# 07_-_QSFP28_1.net
KiCad netlist of a schematic drawn in Altium Designer
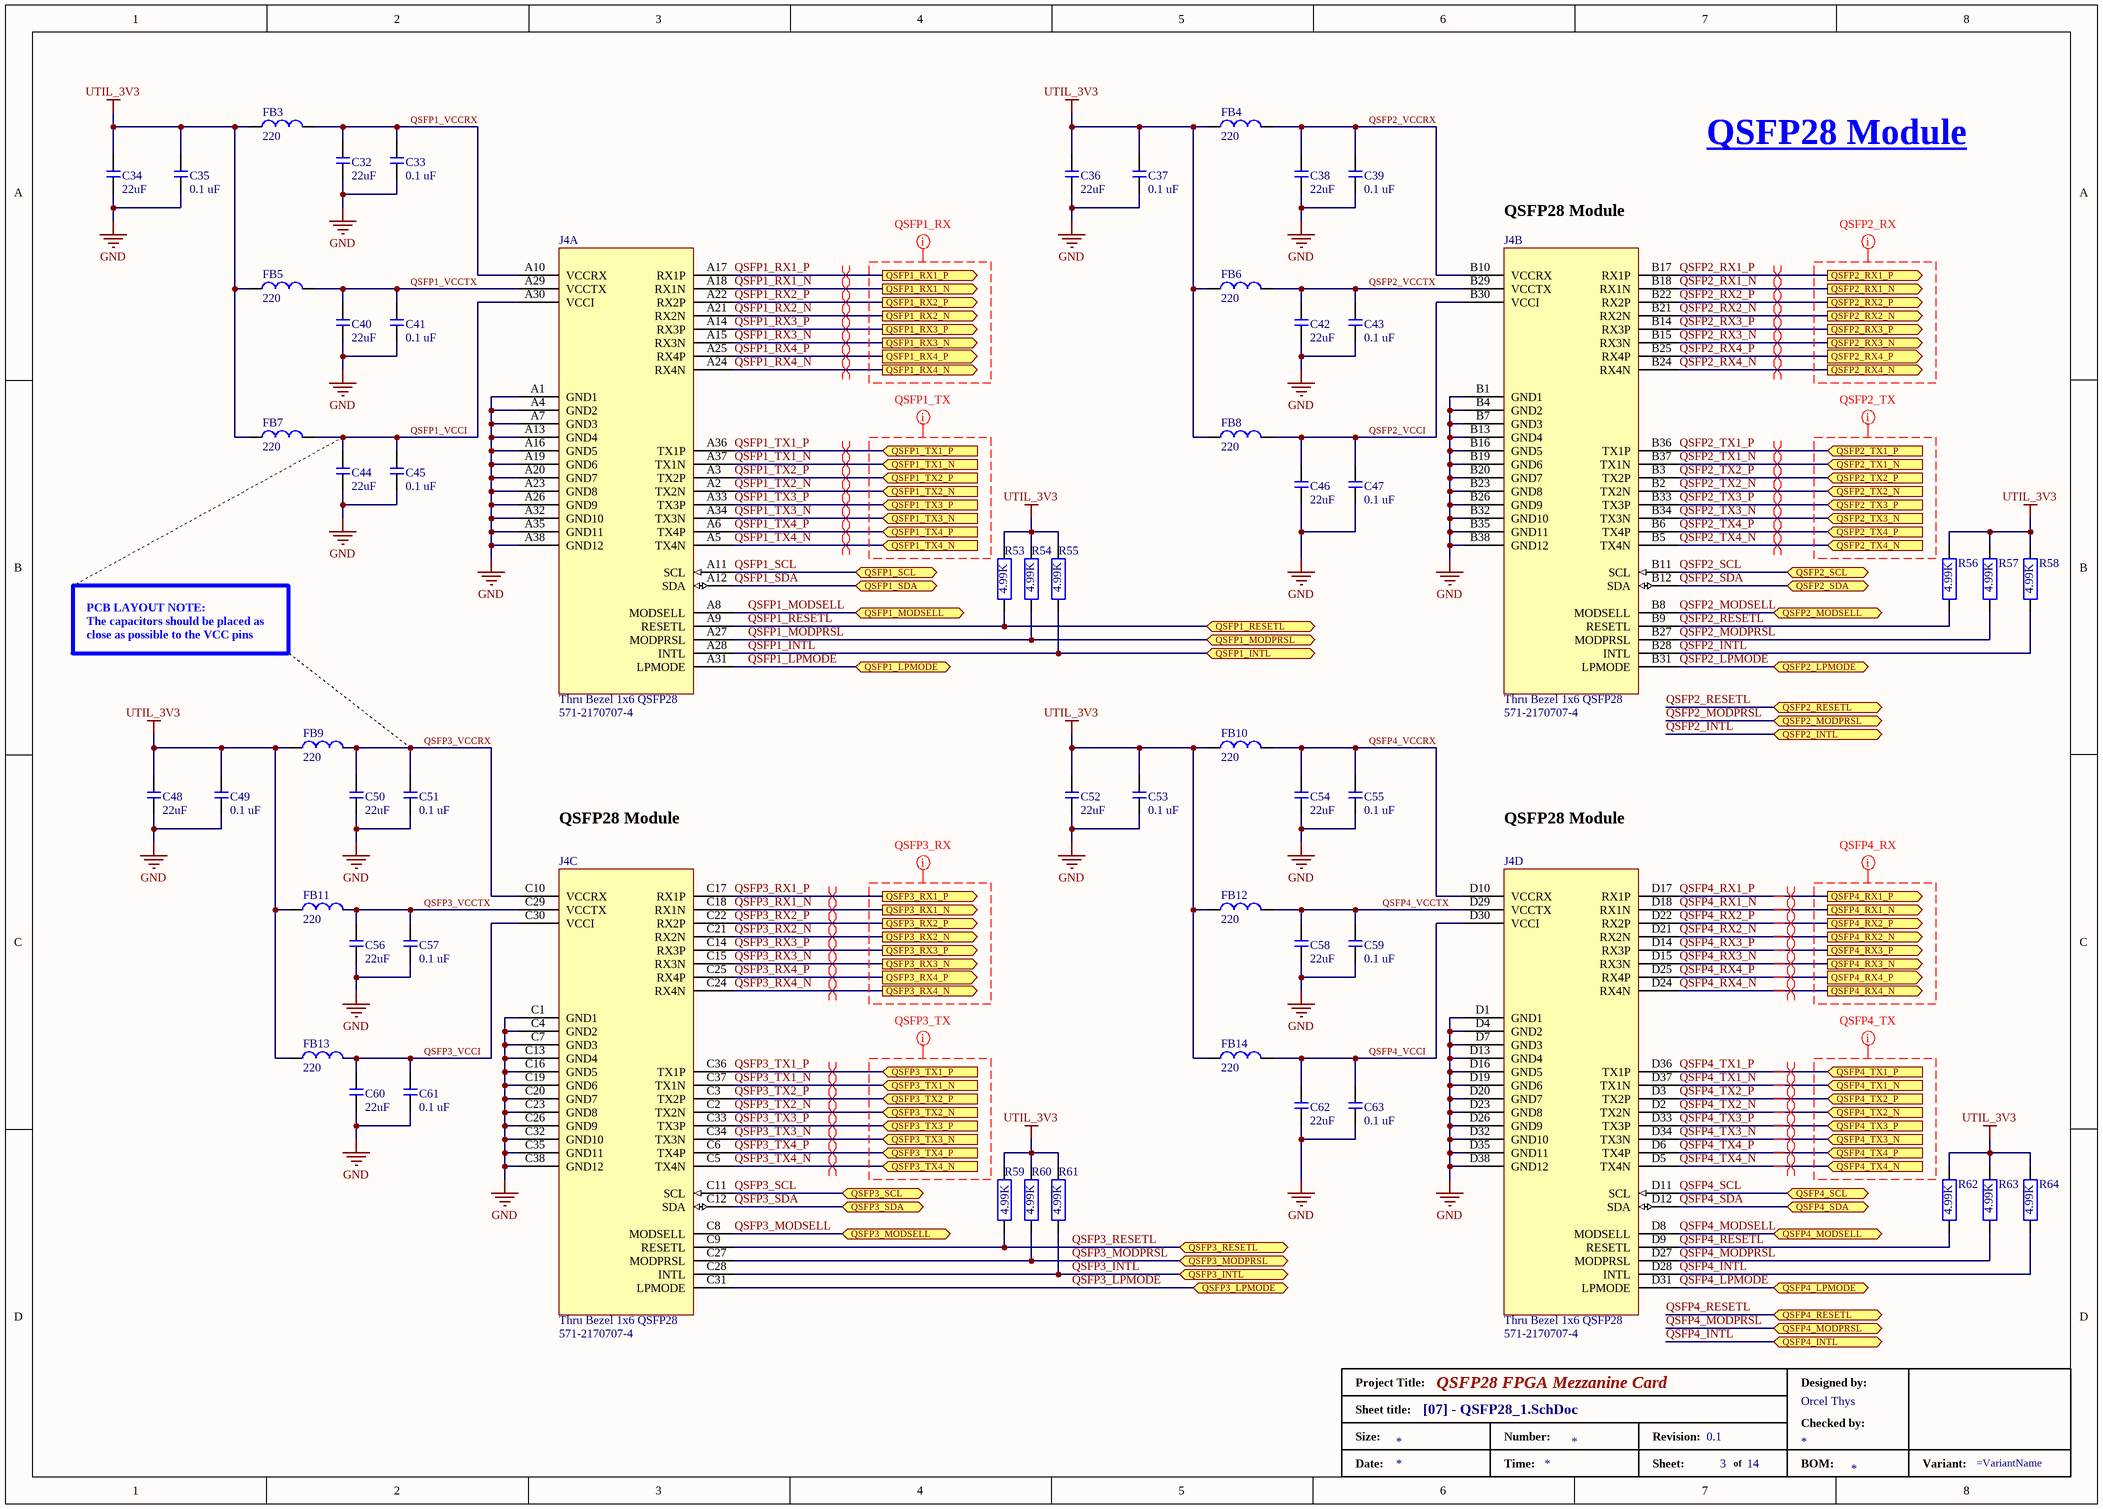
[diagram p0: [07] - QSFP28_1.SchDoc]

(export (version "E")
  (design (tool "Eeschema 10.0.6"))
  (components
    (comp (ref "C32")
      (value "22uF")
      (footprint "C2012")
      (description "Cap Series 0805 22 uF 35 V ±20 % Tolerance X5R SMT Multilayer Ceramic Capacitor")
      (fields
        (field (name "MANUFACTURER") "TDK")
        (field (name "MANUFACTURER PART NUMBER") "C2012X5R1V226M125AC")
      )
      (libsource (lib "QSFP28_FMC_lib") (part "C2012X5R1V226M125AC"))
    )
    (comp (ref "C33")
      (value "0.1 uF")
      (footprint "C0402")
      (description "Cap 0402 0.1 uF 50 V ±10 % Tolerance X7R Surface Mount Multilayer Ceramic Capacitor")
      (fields
        (field (name "MANUFACTURER") "Taiyo Yuden")
        (field (name "MANUFACTURER PART NUMBER") "UMK105B7104KV-FR")
      )
      (libsource (lib "QSFP28_FMC_lib") (part "UMK105B7104KV-FR"))
    )
    (comp (ref "C34")
      (value "22uF")
      (footprint "C2012")
      (description "Cap Series 0805 22 uF 35 V ±20 % Tolerance X5R SMT Multilayer Ceramic Capacitor")
      (fields
        (field (name "MANUFACTURER") "TDK")
        (field (name "MANUFACTURER PART NUMBER") "C2012X5R1V226M125AC")
      )
      (libsource (lib "QSFP28_FMC_lib") (part "C2012X5R1V226M125AC"))
    )
    (comp (ref "C35")
      (value "0.1 uF")
      (footprint "C0402")
      (description "Cap 0402 0.1 uF 50 V ±10 % Tolerance X7R Surface Mount Multilayer Ceramic Capacitor")
      (fields
        (field (name "MANUFACTURER") "Taiyo Yuden")
        (field (name "MANUFACTURER PART NUMBER") "UMK105B7104KV-FR")
      )
      (libsource (lib "QSFP28_FMC_lib") (part "UMK105B7104KV-FR"))
    )
    (comp (ref "C36")
      (value "22uF")
      (footprint "C2012")
      (description "Cap Series 0805 22 uF 35 V ±20 % Tolerance X5R SMT Multilayer Ceramic Capacitor")
      (fields
        (field (name "MANUFACTURER") "TDK")
        (field (name "MANUFACTURER PART NUMBER") "C2012X5R1V226M125AC")
      )
      (libsource (lib "QSFP28_FMC_lib") (part "C2012X5R1V226M125AC"))
    )
    (comp (ref "C37")
      (value "0.1 uF")
      (footprint "C0402")
      (description "Cap 0402 0.1 uF 50 V ±10 % Tolerance X7R Surface Mount Multilayer Ceramic Capacitor")
      (fields
        (field (name "MANUFACTURER") "Taiyo Yuden")
        (field (name "MANUFACTURER PART NUMBER") "UMK105B7104KV-FR")
      )
      (libsource (lib "QSFP28_FMC_lib") (part "UMK105B7104KV-FR"))
    )
    (comp (ref "C38")
      (value "22uF")
      (footprint "C2012")
      (description "Cap Series 0805 22 uF 35 V ±20 % Tolerance X5R SMT Multilayer Ceramic Capacitor")
      (fields
        (field (name "MANUFACTURER") "TDK")
        (field (name "MANUFACTURER PART NUMBER") "C2012X5R1V226M125AC")
      )
      (libsource (lib "QSFP28_FMC_lib") (part "C2012X5R1V226M125AC"))
    )
    (comp (ref "C39")
      (value "0.1 uF")
      (footprint "C0402")
      (description "Cap 0402 0.1 uF 50 V ±10 % Tolerance X7R Surface Mount Multilayer Ceramic Capacitor")
      (fields
        (field (name "MANUFACTURER") "Taiyo Yuden")
        (field (name "MANUFACTURER PART NUMBER") "UMK105B7104KV-FR")
      )
      (libsource (lib "QSFP28_FMC_lib") (part "UMK105B7104KV-FR"))
    )
    (comp (ref "C40")
      (value "22uF")
      (footprint "C2012")
      (description "Cap Series 0805 22 uF 35 V ±20 % Tolerance X5R SMT Multilayer Ceramic Capacitor")
      (fields
        (field (name "MANUFACTURER") "TDK")
        (field (name "MANUFACTURER PART NUMBER") "C2012X5R1V226M125AC")
      )
      (libsource (lib "QSFP28_FMC_lib") (part "C2012X5R1V226M125AC"))
    )
    (comp (ref "C41")
      (value "0.1 uF")
      (footprint "C0402")
      (description "Cap 0402 0.1 uF 50 V ±10 % Tolerance X7R Surface Mount Multilayer Ceramic Capacitor")
      (fields
        (field (name "MANUFACTURER") "Taiyo Yuden")
        (field (name "MANUFACTURER PART NUMBER") "UMK105B7104KV-FR")
      )
      (libsource (lib "QSFP28_FMC_lib") (part "UMK105B7104KV-FR"))
    )
    (comp (ref "C42")
      (value "22uF")
      (footprint "C2012")
      (description "Cap Series 0805 22 uF 35 V ±20 % Tolerance X5R SMT Multilayer Ceramic Capacitor")
      (fields
        (field (name "MANUFACTURER") "TDK")
        (field (name "MANUFACTURER PART NUMBER") "C2012X5R1V226M125AC")
      )
      (libsource (lib "QSFP28_FMC_lib") (part "C2012X5R1V226M125AC"))
    )
    (comp (ref "C43")
      (value "0.1 uF")
      (footprint "C0402")
      (description "Cap 0402 0.1 uF 50 V ±10 % Tolerance X7R Surface Mount Multilayer Ceramic Capacitor")
      (fields
        (field (name "MANUFACTURER") "Taiyo Yuden")
        (field (name "MANUFACTURER PART NUMBER") "UMK105B7104KV-FR")
      )
      (libsource (lib "QSFP28_FMC_lib") (part "UMK105B7104KV-FR"))
    )
    (comp (ref "C44")
      (value "22uF")
      (footprint "C2012")
      (description "Cap Series 0805 22 uF 35 V ±20 % Tolerance X5R SMT Multilayer Ceramic Capacitor")
      (fields
        (field (name "MANUFACTURER") "TDK")
        (field (name "MANUFACTURER PART NUMBER") "C2012X5R1V226M125AC")
      )
      (libsource (lib "QSFP28_FMC_lib") (part "C2012X5R1V226M125AC"))
    )
    (comp (ref "C45")
      (value "0.1 uF")
      (footprint "C0402")
      (description "Cap 0402 0.1 uF 50 V ±10 % Tolerance X7R Surface Mount Multilayer Ceramic Capacitor")
      (fields
        (field (name "MANUFACTURER") "Taiyo Yuden")
        (field (name "MANUFACTURER PART NUMBER") "UMK105B7104KV-FR")
      )
      (libsource (lib "QSFP28_FMC_lib") (part "UMK105B7104KV-FR"))
    )
    (comp (ref "C46")
      (value "22uF")
      (footprint "C2012")
      (description "Cap Series 0805 22 uF 35 V ±20 % Tolerance X5R SMT Multilayer Ceramic Capacitor")
      (fields
        (field (name "MANUFACTURER") "TDK")
        (field (name "MANUFACTURER PART NUMBER") "C2012X5R1V226M125AC")
      )
      (libsource (lib "QSFP28_FMC_lib") (part "C2012X5R1V226M125AC"))
    )
    (comp (ref "C47")
      (value "0.1 uF")
      (footprint "C0402")
      (description "Cap 0402 0.1 uF 50 V ±10 % Tolerance X7R Surface Mount Multilayer Ceramic Capacitor")
      (fields
        (field (name "MANUFACTURER") "Taiyo Yuden")
        (field (name "MANUFACTURER PART NUMBER") "UMK105B7104KV-FR")
      )
      (libsource (lib "QSFP28_FMC_lib") (part "UMK105B7104KV-FR"))
    )
    (comp (ref "C48")
      (value "22uF")
      (footprint "C2012")
      (description "Cap Series 0805 22 uF 35 V ±20 % Tolerance X5R SMT Multilayer Ceramic Capacitor")
      (fields
        (field (name "MANUFACTURER") "TDK")
        (field (name "MANUFACTURER PART NUMBER") "C2012X5R1V226M125AC")
      )
      (libsource (lib "QSFP28_FMC_lib") (part "C2012X5R1V226M125AC"))
    )
    (comp (ref "C49")
      (value "0.1 uF")
      (footprint "C0402")
      (description "Cap 0402 0.1 uF 50 V ±10 % Tolerance X7R Surface Mount Multilayer Ceramic Capacitor")
      (fields
        (field (name "MANUFACTURER") "Taiyo Yuden")
        (field (name "MANUFACTURER PART NUMBER") "UMK105B7104KV-FR")
      )
      (libsource (lib "QSFP28_FMC_lib") (part "UMK105B7104KV-FR"))
    )
    (comp (ref "C50")
      (value "22uF")
      (footprint "C2012")
      (description "Cap Series 0805 22 uF 35 V ±20 % Tolerance X5R SMT Multilayer Ceramic Capacitor")
      (fields
        (field (name "MANUFACTURER") "TDK")
        (field (name "MANUFACTURER PART NUMBER") "C2012X5R1V226M125AC")
      )
      (libsource (lib "QSFP28_FMC_lib") (part "C2012X5R1V226M125AC"))
    )
    (comp (ref "C51")
      (value "0.1 uF")
      (footprint "C0402")
      (description "Cap 0402 0.1 uF 50 V ±10 % Tolerance X7R Surface Mount Multilayer Ceramic Capacitor")
      (fields
        (field (name "MANUFACTURER") "Taiyo Yuden")
        (field (name "MANUFACTURER PART NUMBER") "UMK105B7104KV-FR")
      )
      (libsource (lib "QSFP28_FMC_lib") (part "UMK105B7104KV-FR"))
    )
    (comp (ref "C52")
      (value "22uF")
      (footprint "C2012")
      (description "Cap Series 0805 22 uF 35 V ±20 % Tolerance X5R SMT Multilayer Ceramic Capacitor")
      (fields
        (field (name "MANUFACTURER") "TDK")
        (field (name "MANUFACTURER PART NUMBER") "C2012X5R1V226M125AC")
      )
      (libsource (lib "QSFP28_FMC_lib") (part "C2012X5R1V226M125AC"))
    )
    (comp (ref "C53")
      (value "0.1 uF")
      (footprint "C0402")
      (description "Cap 0402 0.1 uF 50 V ±10 % Tolerance X7R Surface Mount Multilayer Ceramic Capacitor")
      (fields
        (field (name "MANUFACTURER") "Taiyo Yuden")
        (field (name "MANUFACTURER PART NUMBER") "UMK105B7104KV-FR")
      )
      (libsource (lib "QSFP28_FMC_lib") (part "UMK105B7104KV-FR"))
    )
    (comp (ref "C54")
      (value "22uF")
      (footprint "C2012")
      (description "Cap Series 0805 22 uF 35 V ±20 % Tolerance X5R SMT Multilayer Ceramic Capacitor")
      (fields
        (field (name "MANUFACTURER") "TDK")
        (field (name "MANUFACTURER PART NUMBER") "C2012X5R1V226M125AC")
      )
      (libsource (lib "QSFP28_FMC_lib") (part "C2012X5R1V226M125AC"))
    )
    (comp (ref "C55")
      (value "0.1 uF")
      (footprint "C0402")
      (description "Cap 0402 0.1 uF 50 V ±10 % Tolerance X7R Surface Mount Multilayer Ceramic Capacitor")
      (fields
        (field (name "MANUFACTURER") "Taiyo Yuden")
        (field (name "MANUFACTURER PART NUMBER") "UMK105B7104KV-FR")
      )
      (libsource (lib "QSFP28_FMC_lib") (part "UMK105B7104KV-FR"))
    )
    (comp (ref "C56")
      (value "22uF")
      (footprint "C2012")
      (description "Cap Series 0805 22 uF 35 V ±20 % Tolerance X5R SMT Multilayer Ceramic Capacitor")
      (fields
        (field (name "MANUFACTURER") "TDK")
        (field (name "MANUFACTURER PART NUMBER") "C2012X5R1V226M125AC")
      )
      (libsource (lib "QSFP28_FMC_lib") (part "C2012X5R1V226M125AC"))
    )
    (comp (ref "C57")
      (value "0.1 uF")
      (footprint "C0402")
      (description "Cap 0402 0.1 uF 50 V ±10 % Tolerance X7R Surface Mount Multilayer Ceramic Capacitor")
      (fields
        (field (name "MANUFACTURER") "Taiyo Yuden")
        (field (name "MANUFACTURER PART NUMBER") "UMK105B7104KV-FR")
      )
      (libsource (lib "QSFP28_FMC_lib") (part "UMK105B7104KV-FR"))
    )
    (comp (ref "C58")
      (value "22uF")
      (footprint "C2012")
      (description "Cap Series 0805 22 uF 35 V ±20 % Tolerance X5R SMT Multilayer Ceramic Capacitor")
      (fields
        (field (name "MANUFACTURER") "TDK")
        (field (name "MANUFACTURER PART NUMBER") "C2012X5R1V226M125AC")
      )
      (libsource (lib "QSFP28_FMC_lib") (part "C2012X5R1V226M125AC"))
    )
    (comp (ref "C59")
      (value "0.1 uF")
      (footprint "C0402")
      (description "Cap 0402 0.1 uF 50 V ±10 % Tolerance X7R Surface Mount Multilayer Ceramic Capacitor")
      (fields
        (field (name "MANUFACTURER") "Taiyo Yuden")
        (field (name "MANUFACTURER PART NUMBER") "UMK105B7104KV-FR")
      )
      (libsource (lib "QSFP28_FMC_lib") (part "UMK105B7104KV-FR"))
    )
    (comp (ref "C60")
      (value "22uF")
      (footprint "C2012")
      (description "Cap Series 0805 22 uF 35 V ±20 % Tolerance X5R SMT Multilayer Ceramic Capacitor")
      (fields
        (field (name "MANUFACTURER") "TDK")
        (field (name "MANUFACTURER PART NUMBER") "C2012X5R1V226M125AC")
      )
      (libsource (lib "QSFP28_FMC_lib") (part "C2012X5R1V226M125AC"))
    )
    (comp (ref "C61")
      (value "0.1 uF")
      (footprint "C0402")
      (description "Cap 0402 0.1 uF 50 V ±10 % Tolerance X7R Surface Mount Multilayer Ceramic Capacitor")
      (fields
        (field (name "MANUFACTURER") "Taiyo Yuden")
        (field (name "MANUFACTURER PART NUMBER") "UMK105B7104KV-FR")
      )
      (libsource (lib "QSFP28_FMC_lib") (part "UMK105B7104KV-FR"))
    )
    (comp (ref "C62")
      (value "22uF")
      (footprint "C2012")
      (description "Cap Series 0805 22 uF 35 V ±20 % Tolerance X5R SMT Multilayer Ceramic Capacitor")
      (fields
        (field (name "MANUFACTURER") "TDK")
        (field (name "MANUFACTURER PART NUMBER") "C2012X5R1V226M125AC")
      )
      (libsource (lib "QSFP28_FMC_lib") (part "C2012X5R1V226M125AC"))
    )
    (comp (ref "C63")
      (value "0.1 uF")
      (footprint "C0402")
      (description "Cap 0402 0.1 uF 50 V ±10 % Tolerance X7R Surface Mount Multilayer Ceramic Capacitor")
      (fields
        (field (name "MANUFACTURER") "Taiyo Yuden")
        (field (name "MANUFACTURER PART NUMBER") "UMK105B7104KV-FR")
      )
      (libsource (lib "QSFP28_FMC_lib") (part "UMK105B7104KV-FR"))
    )
    (comp (ref "FB3")
      (value "220")
      (footprint "BEADC1608X75N")
      (description "0603 220Ω ±25% DCR=0.050Ω 2.2A")
      (fields
        (field (name "MANUFACTURER") "TDK")
        (field (name "MANUFACTURER PART NUMBER") "MPZ1608S221ATA00")
      )
      (libsource (lib "QSFP28_FMC_lib") (part "MPZ1608S221ATA00"))
    )
    (comp (ref "FB4")
      (value "220")
      (footprint "BEADC1608X75N")
      (description "0603 220Ω ±25% DCR=0.050Ω 2.2A")
      (fields
        (field (name "MANUFACTURER") "TDK")
        (field (name "MANUFACTURER PART NUMBER") "MPZ1608S221ATA00")
      )
      (libsource (lib "QSFP28_FMC_lib") (part "MPZ1608S221ATA00"))
    )
    (comp (ref "FB5")
      (value "220")
      (footprint "BEADC1608X75N")
      (description "0603 220Ω ±25% DCR=0.050Ω 2.2A")
      (fields
        (field (name "MANUFACTURER") "TDK")
        (field (name "MANUFACTURER PART NUMBER") "MPZ1608S221ATA00")
      )
      (libsource (lib "QSFP28_FMC_lib") (part "MPZ1608S221ATA00"))
    )
    (comp (ref "FB6")
      (value "220")
      (footprint "BEADC1608X75N")
      (description "0603 220Ω ±25% DCR=0.050Ω 2.2A")
      (fields
        (field (name "MANUFACTURER") "TDK")
        (field (name "MANUFACTURER PART NUMBER") "MPZ1608S221ATA00")
      )
      (libsource (lib "QSFP28_FMC_lib") (part "MPZ1608S221ATA00"))
    )
    (comp (ref "FB7")
      (value "220")
      (footprint "BEADC1608X75N")
      (description "0603 220Ω ±25% DCR=0.050Ω 2.2A")
      (fields
        (field (name "MANUFACTURER") "TDK")
        (field (name "MANUFACTURER PART NUMBER") "MPZ1608S221ATA00")
      )
      (libsource (lib "QSFP28_FMC_lib") (part "MPZ1608S221ATA00"))
    )
    (comp (ref "FB8")
      (value "220")
      (footprint "BEADC1608X75N")
      (description "0603 220Ω ±25% DCR=0.050Ω 2.2A")
      (fields
        (field (name "MANUFACTURER") "TDK")
        (field (name "MANUFACTURER PART NUMBER") "MPZ1608S221ATA00")
      )
      (libsource (lib "QSFP28_FMC_lib") (part "MPZ1608S221ATA00"))
    )
    (comp (ref "FB9")
      (value "220")
      (footprint "BEADC1608X75N")
      (description "0603 220Ω ±25% DCR=0.050Ω 2.2A")
      (fields
        (field (name "MANUFACTURER") "TDK")
        (field (name "MANUFACTURER PART NUMBER") "MPZ1608S221ATA00")
      )
      (libsource (lib "QSFP28_FMC_lib") (part "MPZ1608S221ATA00"))
    )
    (comp (ref "FB10")
      (value "220")
      (footprint "BEADC1608X75N")
      (description "0603 220Ω ±25% DCR=0.050Ω 2.2A")
      (fields
        (field (name "MANUFACTURER") "TDK")
        (field (name "MANUFACTURER PART NUMBER") "MPZ1608S221ATA00")
      )
      (libsource (lib "QSFP28_FMC_lib") (part "MPZ1608S221ATA00"))
    )
    (comp (ref "FB11")
      (value "220")
      (footprint "BEADC1608X75N")
      (description "0603 220Ω ±25% DCR=0.050Ω 2.2A")
      (fields
        (field (name "MANUFACTURER") "TDK")
        (field (name "MANUFACTURER PART NUMBER") "MPZ1608S221ATA00")
      )
      (libsource (lib "QSFP28_FMC_lib") (part "MPZ1608S221ATA00"))
    )
    (comp (ref "FB12")
      (value "220")
      (footprint "BEADC1608X75N")
      (description "0603 220Ω ±25% DCR=0.050Ω 2.2A")
      (fields
        (field (name "MANUFACTURER") "TDK")
        (field (name "MANUFACTURER PART NUMBER") "MPZ1608S221ATA00")
      )
      (libsource (lib "QSFP28_FMC_lib") (part "MPZ1608S221ATA00"))
    )
    (comp (ref "FB13")
      (value "220")
      (footprint "BEADC1608X75N")
      (description "0603 220Ω ±25% DCR=0.050Ω 2.2A")
      (fields
        (field (name "MANUFACTURER") "TDK")
        (field (name "MANUFACTURER PART NUMBER") "MPZ1608S221ATA00")
      )
      (libsource (lib "QSFP28_FMC_lib") (part "MPZ1608S221ATA00"))
    )
    (comp (ref "FB14")
      (value "220")
      (footprint "BEADC1608X75N")
      (description "0603 220Ω ±25% DCR=0.050Ω 2.2A")
      (fields
        (field (name "MANUFACTURER") "TDK")
        (field (name "MANUFACTURER PART NUMBER") "MPZ1608S221ATA00")
      )
      (libsource (lib "QSFP28_FMC_lib") (part "MPZ1608S221ATA00"))
    )
    (comp (ref "J4")
      (value "Thru Bezel 1x6 QSFP28")
      (footprint "TE_2170707-4")
      (description "Cage Assy, 1X6, QSFP28, Spring, Hs")
      (fields
        (field (name "MANUFACTURER") "TE Connectivity AMP")
        (field (name "MANUFACTURER PART NUMBER") "2170707-4")
        (field (name "SUPPLIER PART NUMBER 1") "571-2170707-4")
      )
      (libsource (lib "QSFP28_FMC_lib") (part "2170707-4"))
    )
    (comp (ref "R53")
      (value "4.99K")
      (footprint "R0402")
      (description "RES SMD 4.99K OHM 1% 1/10W 0402")
      (fields
        (field (name "MANUFACTURER") "Panasonic")
        (field (name "MANUFACTURER PART NUMBER") "ERJ-2RKF4991X")
      )
      (libsource (lib "QSFP28_FMC_lib") (part "ERJ-2RKF4991X"))
    )
    (comp (ref "R54")
      (value "4.99K")
      (footprint "R0402")
      (description "RES SMD 4.99K OHM 1% 1/10W 0402")
      (fields
        (field (name "MANUFACTURER") "Panasonic")
        (field (name "MANUFACTURER PART NUMBER") "ERJ-2RKF4991X")
      )
      (libsource (lib "QSFP28_FMC_lib") (part "ERJ-2RKF4991X"))
    )
    (comp (ref "R55")
      (value "4.99K")
      (footprint "R0402")
      (description "RES SMD 4.99K OHM 1% 1/10W 0402")
      (fields
        (field (name "MANUFACTURER") "Panasonic")
        (field (name "MANUFACTURER PART NUMBER") "ERJ-2RKF4991X")
      )
      (libsource (lib "QSFP28_FMC_lib") (part "ERJ-2RKF4991X"))
    )
    (comp (ref "R56")
      (value "4.99K")
      (footprint "R0402")
      (description "RES SMD 4.99K OHM 1% 1/10W 0402")
      (fields
        (field (name "MANUFACTURER") "Panasonic")
        (field (name "MANUFACTURER PART NUMBER") "ERJ-2RKF4991X")
      )
      (libsource (lib "QSFP28_FMC_lib") (part "ERJ-2RKF4991X"))
    )
    (comp (ref "R57")
      (value "4.99K")
      (footprint "R0402")
      (description "RES SMD 4.99K OHM 1% 1/10W 0402")
      (fields
        (field (name "MANUFACTURER") "Panasonic")
        (field (name "MANUFACTURER PART NUMBER") "ERJ-2RKF4991X")
      )
      (libsource (lib "QSFP28_FMC_lib") (part "ERJ-2RKF4991X"))
    )
    (comp (ref "R58")
      (value "4.99K")
      (footprint "R0402")
      (description "RES SMD 4.99K OHM 1% 1/10W 0402")
      (fields
        (field (name "MANUFACTURER") "Panasonic")
        (field (name "MANUFACTURER PART NUMBER") "ERJ-2RKF4991X")
      )
      (libsource (lib "QSFP28_FMC_lib") (part "ERJ-2RKF4991X"))
    )
    (comp (ref "R59")
      (value "4.99K")
      (footprint "R0402")
      (description "RES SMD 4.99K OHM 1% 1/10W 0402")
      (fields
        (field (name "MANUFACTURER") "Panasonic")
        (field (name "MANUFACTURER PART NUMBER") "ERJ-2RKF4991X")
      )
      (libsource (lib "QSFP28_FMC_lib") (part "ERJ-2RKF4991X"))
    )
    (comp (ref "R60")
      (value "4.99K")
      (footprint "R0402")
      (description "RES SMD 4.99K OHM 1% 1/10W 0402")
      (fields
        (field (name "MANUFACTURER") "Panasonic")
        (field (name "MANUFACTURER PART NUMBER") "ERJ-2RKF4991X")
      )
      (libsource (lib "QSFP28_FMC_lib") (part "ERJ-2RKF4991X"))
    )
    (comp (ref "R61")
      (value "4.99K")
      (footprint "R0402")
      (description "RES SMD 4.99K OHM 1% 1/10W 0402")
      (fields
        (field (name "MANUFACTURER") "Panasonic")
        (field (name "MANUFACTURER PART NUMBER") "ERJ-2RKF4991X")
      )
      (libsource (lib "QSFP28_FMC_lib") (part "ERJ-2RKF4991X"))
    )
    (comp (ref "R62")
      (value "4.99K")
      (footprint "R0402")
      (description "RES SMD 4.99K OHM 1% 1/10W 0402")
      (fields
        (field (name "MANUFACTURER") "Panasonic")
        (field (name "MANUFACTURER PART NUMBER") "ERJ-2RKF4991X")
      )
      (libsource (lib "QSFP28_FMC_lib") (part "ERJ-2RKF4991X"))
    )
    (comp (ref "R63")
      (value "4.99K")
      (footprint "R0402")
      (description "RES SMD 4.99K OHM 1% 1/10W 0402")
      (fields
        (field (name "MANUFACTURER") "Panasonic")
        (field (name "MANUFACTURER PART NUMBER") "ERJ-2RKF4991X")
      )
      (libsource (lib "QSFP28_FMC_lib") (part "ERJ-2RKF4991X"))
    )
    (comp (ref "R64")
      (value "4.99K")
      (footprint "R0402")
      (description "RES SMD 4.99K OHM 1% 1/10W 0402")
      (fields
        (field (name "MANUFACTURER") "Panasonic")
        (field (name "MANUFACTURER PART NUMBER") "ERJ-2RKF4991X")
      )
      (libsource (lib "QSFP28_FMC_lib") (part "ERJ-2RKF4991X"))
    )
  )
  (nets
    (net (code "1") (name "/QSFP1_INTL") (class "Default")
      (node (ref "J4") (pin "A28") (pinfunction "INTL_A28") (pintype "passive"))
      (node (ref "R55") (pin "1") (pintype "passive"))
    )
    (net (code "2") (name "/QSFP1_LPMODE") (class "Default")
      (node (ref "J4") (pin "A31") (pinfunction "LPMODE_A31") (pintype "passive"))
    )
    (net (code "3") (name "/QSFP1_MODPRSL") (class "Default")
      (node (ref "J4") (pin "A27") (pinfunction "MODPRSL_A27") (pintype "passive"))
      (node (ref "R54") (pin "1") (pintype "passive"))
    )
    (net (code "4") (name "/QSFP1_MODSELL") (class "Default")
      (node (ref "J4") (pin "A8") (pinfunction "MODSELL_A8") (pintype "passive"))
    )
    (net (code "5") (name "/QSFP1_RESETL") (class "Default")
      (node (ref "J4") (pin "A9") (pinfunction "RESETL_A9") (pintype "passive"))
      (node (ref "R53") (pin "1") (pintype "passive"))
    )
    (net (code "6") (name "/QSFP1_RX1_N") (class "Default")
      (node (ref "J4") (pin "A18") (pinfunction "RX1N_A18") (pintype "passive"))
    )
    (net (code "7") (name "/QSFP1_RX1_P") (class "Default")
      (node (ref "J4") (pin "A17") (pinfunction "RX1P_A17") (pintype "passive"))
    )
    (net (code "8") (name "/QSFP1_RX2_N") (class "Default")
      (node (ref "J4") (pin "A21") (pinfunction "RX2N_A21") (pintype "passive"))
    )
    (net (code "9") (name "/QSFP1_RX2_P") (class "Default")
      (node (ref "J4") (pin "A22") (pinfunction "RX2P_A22") (pintype "passive"))
    )
    (net (code "10") (name "/QSFP1_RX3_N") (class "Default")
      (node (ref "J4") (pin "A15") (pinfunction "RX3N_A15") (pintype "passive"))
    )
    (net (code "11") (name "/QSFP1_RX3_P") (class "Default")
      (node (ref "J4") (pin "A14") (pinfunction "RX3P_A14") (pintype "passive"))
    )
    (net (code "12") (name "/QSFP1_RX4_N") (class "Default")
      (node (ref "J4") (pin "A24") (pinfunction "RX4N_A24") (pintype "passive"))
    )
    (net (code "13") (name "/QSFP1_RX4_P") (class "Default")
      (node (ref "J4") (pin "A25") (pinfunction "RX4P_A25") (pintype "passive"))
    )
    (net (code "14") (name "/QSFP1_SCL") (class "Default")
      (node (ref "J4") (pin "A11") (pinfunction "SCL_A11") (pintype "input"))
    )
    (net (code "15") (name "/QSFP1_SDA") (class "Default")
      (node (ref "J4") (pin "A12") (pinfunction "SDA_A12") (pintype "bidirectional"))
    )
    (net (code "16") (name "/QSFP1_TX1_N") (class "Default")
      (node (ref "J4") (pin "A37") (pinfunction "TX1N_A37") (pintype "passive"))
    )
    (net (code "17") (name "/QSFP1_TX1_P") (class "Default")
      (node (ref "J4") (pin "A36") (pinfunction "TX1P_A36") (pintype "passive"))
    )
    (net (code "18") (name "/QSFP1_TX2_N") (class "Default")
      (node (ref "J4") (pin "A2") (pinfunction "TX2N_A2") (pintype "passive"))
    )
    (net (code "19") (name "/QSFP1_TX2_P") (class "Default")
      (node (ref "J4") (pin "A3") (pinfunction "TX2P_A3") (pintype "passive"))
    )
    (net (code "20") (name "/QSFP1_TX3_N") (class "Default")
      (node (ref "J4") (pin "A34") (pinfunction "TX3N_A34") (pintype "passive"))
    )
    (net (code "21") (name "/QSFP1_TX3_P") (class "Default")
      (node (ref "J4") (pin "A33") (pinfunction "TX3P_A33") (pintype "passive"))
    )
    (net (code "22") (name "/QSFP1_TX4_N") (class "Default")
      (node (ref "J4") (pin "A5") (pinfunction "TX4N_A5") (pintype "passive"))
    )
    (net (code "23") (name "/QSFP1_TX4_P") (class "Default")
      (node (ref "J4") (pin "A6") (pinfunction "TX4P_A6") (pintype "passive"))
    )
    (net (code "24") (name "/QSFP1_VCCI") (class "Default")
      (node (ref "C44") (pin "2") (pinfunction "2_2") (pintype "passive"))
      (node (ref "C45") (pin "2") (pinfunction "2_2") (pintype "passive"))
      (node (ref "FB7") (pin "2") (pintype "passive"))
      (node (ref "J4") (pin "A30") (pinfunction "VCCI_A30") (pintype "power_in"))
    )
    (net (code "25") (name "/QSFP1_VCCRX") (class "Default")
      (node (ref "C32") (pin "2") (pinfunction "2_2") (pintype "passive"))
      (node (ref "C33") (pin "2") (pinfunction "2_2") (pintype "passive"))
      (node (ref "FB3") (pin "2") (pintype "passive"))
      (node (ref "J4") (pin "A10") (pinfunction "VCCRX_A10") (pintype "power_in"))
    )
    (net (code "26") (name "/QSFP1_VCCTX") (class "Default")
      (node (ref "C40") (pin "2") (pinfunction "2_2") (pintype "passive"))
      (node (ref "C41") (pin "2") (pinfunction "2_2") (pintype "passive"))
      (node (ref "FB5") (pin "2") (pintype "passive"))
      (node (ref "J4") (pin "A29") (pinfunction "VCCTX_A29") (pintype "power_in"))
    )
    (net (code "27") (name "/QSFP2_INTL") (class "Default")
      (node (ref "J4") (pin "B28") (pinfunction "INTL_B28") (pintype "passive"))
      (node (ref "R58") (pin "1") (pintype "passive"))
    )
    (net (code "28") (name "/QSFP2_LPMODE") (class "Default")
      (node (ref "J4") (pin "B31") (pinfunction "LPMODE_B31") (pintype "passive"))
    )
    (net (code "29") (name "/QSFP2_MODPRSL") (class "Default")
      (node (ref "J4") (pin "B27") (pinfunction "MODPRSL_B27") (pintype "passive"))
      (node (ref "R57") (pin "1") (pintype "passive"))
    )
    (net (code "30") (name "/QSFP2_MODSELL") (class "Default")
      (node (ref "J4") (pin "B8") (pinfunction "MODSELL_B8") (pintype "passive"))
    )
    (net (code "31") (name "/QSFP2_RESETL") (class "Default")
      (node (ref "J4") (pin "B9") (pinfunction "RESETL_B9") (pintype "passive"))
      (node (ref "R56") (pin "1") (pintype "passive"))
    )
    (net (code "32") (name "/QSFP2_RX1_N") (class "Default")
      (node (ref "J4") (pin "B18") (pinfunction "RX1N_B18") (pintype "passive"))
    )
    (net (code "33") (name "/QSFP2_RX1_P") (class "Default")
      (node (ref "J4") (pin "B17") (pinfunction "RX1P_B17") (pintype "passive"))
    )
    (net (code "34") (name "/QSFP2_RX2_N") (class "Default")
      (node (ref "J4") (pin "B21") (pinfunction "RX2N_B21") (pintype "passive"))
    )
    (net (code "35") (name "/QSFP2_RX2_P") (class "Default")
      (node (ref "J4") (pin "B22") (pinfunction "RX2P_B22") (pintype "passive"))
    )
    (net (code "36") (name "/QSFP2_RX3_N") (class "Default")
      (node (ref "J4") (pin "B15") (pinfunction "RX3N_B15") (pintype "passive"))
    )
    (net (code "37") (name "/QSFP2_RX3_P") (class "Default")
      (node (ref "J4") (pin "B14") (pinfunction "RX3P_B14") (pintype "passive"))
    )
    (net (code "38") (name "/QSFP2_RX4_N") (class "Default")
      (node (ref "J4") (pin "B24") (pinfunction "RX4N_B24") (pintype "passive"))
    )
    (net (code "39") (name "/QSFP2_RX4_P") (class "Default")
      (node (ref "J4") (pin "B25") (pinfunction "RX4P_B25") (pintype "passive"))
    )
    (net (code "40") (name "/QSFP2_SCL") (class "Default")
      (node (ref "J4") (pin "B11") (pinfunction "SCL_B11") (pintype "input"))
    )
    (net (code "41") (name "/QSFP2_SDA") (class "Default")
      (node (ref "J4") (pin "B12") (pinfunction "SDA_B12") (pintype "bidirectional"))
    )
    (net (code "42") (name "/QSFP2_TX1_N") (class "Default")
      (node (ref "J4") (pin "B37") (pinfunction "TX1N_B37") (pintype "passive"))
    )
    (net (code "43") (name "/QSFP2_TX1_P") (class "Default")
      (node (ref "J4") (pin "B36") (pinfunction "TX1P_B36") (pintype "passive"))
    )
    (net (code "44") (name "/QSFP2_TX2_N") (class "Default")
      (node (ref "J4") (pin "B2") (pinfunction "TX2N_B2") (pintype "passive"))
    )
    (net (code "45") (name "/QSFP2_TX2_P") (class "Default")
      (node (ref "J4") (pin "B3") (pinfunction "TX2P_B3") (pintype "passive"))
    )
    (net (code "46") (name "/QSFP2_TX3_N") (class "Default")
      (node (ref "J4") (pin "B34") (pinfunction "TX3N_B34") (pintype "passive"))
    )
    (net (code "47") (name "/QSFP2_TX3_P") (class "Default")
      (node (ref "J4") (pin "B33") (pinfunction "TX3P_B33") (pintype "passive"))
    )
    (net (code "48") (name "/QSFP2_TX4_N") (class "Default")
      (node (ref "J4") (pin "B5") (pinfunction "TX4N_B5") (pintype "passive"))
    )
    (net (code "49") (name "/QSFP2_TX4_P") (class "Default")
      (node (ref "J4") (pin "B6") (pinfunction "TX4P_B6") (pintype "passive"))
    )
    (net (code "50") (name "/QSFP2_VCCI") (class "Default")
      (node (ref "C46") (pin "2") (pinfunction "2_2") (pintype "passive"))
      (node (ref "C47") (pin "2") (pinfunction "2_2") (pintype "passive"))
      (node (ref "FB8") (pin "2") (pintype "passive"))
      (node (ref "J4") (pin "B30") (pinfunction "VCCI_B30") (pintype "power_in"))
    )
    (net (code "51") (name "/QSFP2_VCCRX") (class "Default")
      (node (ref "C38") (pin "2") (pinfunction "2_2") (pintype "passive"))
      (node (ref "C39") (pin "2") (pinfunction "2_2") (pintype "passive"))
      (node (ref "FB4") (pin "2") (pintype "passive"))
      (node (ref "J4") (pin "B10") (pinfunction "VCCRX_B10") (pintype "power_in"))
    )
    (net (code "52") (name "/QSFP2_VCCTX") (class "Default")
      (node (ref "C42") (pin "2") (pinfunction "2_2") (pintype "passive"))
      (node (ref "C43") (pin "2") (pinfunction "2_2") (pintype "passive"))
      (node (ref "FB6") (pin "2") (pintype "passive"))
      (node (ref "J4") (pin "B29") (pinfunction "VCCTX_B29") (pintype "power_in"))
    )
    (net (code "53") (name "/QSFP3_INTL") (class "Default")
      (node (ref "J4") (pin "C28") (pinfunction "INTL_C28") (pintype "passive"))
      (node (ref "R61") (pin "1") (pintype "passive"))
    )
    (net (code "54") (name "/QSFP3_LPMODE") (class "Default")
      (node (ref "J4") (pin "C31") (pinfunction "LPMODE_C31") (pintype "passive"))
    )
    (net (code "55") (name "/QSFP3_MODPRSL") (class "Default")
      (node (ref "J4") (pin "C27") (pinfunction "MODPRSL_C27") (pintype "passive"))
      (node (ref "R60") (pin "1") (pintype "passive"))
    )
    (net (code "56") (name "/QSFP3_MODSELL") (class "Default")
      (node (ref "J4") (pin "C8") (pinfunction "MODSELL_C8") (pintype "passive"))
    )
    (net (code "57") (name "/QSFP3_RESETL") (class "Default")
      (node (ref "J4") (pin "C9") (pinfunction "RESETL_C9") (pintype "passive"))
      (node (ref "R59") (pin "1") (pintype "passive"))
    )
    (net (code "58") (name "/QSFP3_RX1_N") (class "Default")
      (node (ref "J4") (pin "C18") (pinfunction "RX1N_C18") (pintype "passive"))
    )
    (net (code "59") (name "/QSFP3_RX1_P") (class "Default")
      (node (ref "J4") (pin "C17") (pinfunction "RX1P_C17") (pintype "passive"))
    )
    (net (code "60") (name "/QSFP3_RX2_N") (class "Default")
      (node (ref "J4") (pin "C21") (pinfunction "RX2N_C21") (pintype "passive"))
    )
    (net (code "61") (name "/QSFP3_RX2_P") (class "Default")
      (node (ref "J4") (pin "C22") (pinfunction "RX2P_C22") (pintype "passive"))
    )
    (net (code "62") (name "/QSFP3_RX3_N") (class "Default")
      (node (ref "J4") (pin "C15") (pinfunction "RX3N_C15") (pintype "passive"))
    )
    (net (code "63") (name "/QSFP3_RX3_P") (class "Default")
      (node (ref "J4") (pin "C14") (pinfunction "RX3P_C14") (pintype "passive"))
    )
    (net (code "64") (name "/QSFP3_RX4_N") (class "Default")
      (node (ref "J4") (pin "C24") (pinfunction "RX4N_C24") (pintype "passive"))
    )
    (net (code "65") (name "/QSFP3_RX4_P") (class "Default")
      (node (ref "J4") (pin "C25") (pinfunction "RX4P_C25") (pintype "passive"))
    )
    (net (code "66") (name "/QSFP3_SCL") (class "Default")
      (node (ref "J4") (pin "C11") (pinfunction "SCL_C11") (pintype "input"))
    )
    (net (code "67") (name "/QSFP3_SDA") (class "Default")
      (node (ref "J4") (pin "C12") (pinfunction "SDA_C12") (pintype "bidirectional"))
    )
    (net (code "68") (name "/QSFP3_TX1_N") (class "Default")
      (node (ref "J4") (pin "C37") (pinfunction "TX1N_C37") (pintype "passive"))
    )
    (net (code "69") (name "/QSFP3_TX1_P") (class "Default")
      (node (ref "J4") (pin "C36") (pinfunction "TX1P_C36") (pintype "passive"))
    )
    (net (code "70") (name "/QSFP3_TX2_N") (class "Default")
      (node (ref "J4") (pin "C2") (pinfunction "TX2N_C2") (pintype "passive"))
    )
    (net (code "71") (name "/QSFP3_TX2_P") (class "Default")
      (node (ref "J4") (pin "C3") (pinfunction "TX2P_C3") (pintype "passive"))
    )
    (net (code "72") (name "/QSFP3_TX3_N") (class "Default")
      (node (ref "J4") (pin "C34") (pinfunction "TX3N_C34") (pintype "passive"))
    )
    (net (code "73") (name "/QSFP3_TX3_P") (class "Default")
      (node (ref "J4") (pin "C33") (pinfunction "TX3P_C33") (pintype "passive"))
    )
    (net (code "74") (name "/QSFP3_TX4_N") (class "Default")
      (node (ref "J4") (pin "C5") (pinfunction "TX4N_C5") (pintype "passive"))
    )
    (net (code "75") (name "/QSFP3_TX4_P") (class "Default")
      (node (ref "J4") (pin "C6") (pinfunction "TX4P_C6") (pintype "passive"))
    )
    (net (code "76") (name "/QSFP3_VCCI") (class "Default")
      (node (ref "C60") (pin "2") (pinfunction "2_2") (pintype "passive"))
      (node (ref "C61") (pin "2") (pinfunction "2_2") (pintype "passive"))
      (node (ref "FB13") (pin "2") (pintype "passive"))
      (node (ref "J4") (pin "C30") (pinfunction "VCCI_C30") (pintype "power_in"))
    )
    (net (code "77") (name "/QSFP3_VCCRX") (class "Default")
      (node (ref "C50") (pin "2") (pinfunction "2_2") (pintype "passive"))
      (node (ref "C51") (pin "2") (pinfunction "2_2") (pintype "passive"))
      (node (ref "FB9") (pin "2") (pintype "passive"))
      (node (ref "J4") (pin "C10") (pinfunction "VCCRX_C10") (pintype "power_in"))
    )
    (net (code "78") (name "/QSFP3_VCCTX") (class "Default")
      (node (ref "C56") (pin "2") (pinfunction "2_2") (pintype "passive"))
      (node (ref "C57") (pin "2") (pinfunction "2_2") (pintype "passive"))
      (node (ref "FB11") (pin "2") (pintype "passive"))
      (node (ref "J4") (pin "C29") (pinfunction "VCCTX_C29") (pintype "power_in"))
    )
    (net (code "79") (name "/QSFP4_INTL") (class "Default")
      (node (ref "J4") (pin "D28") (pinfunction "INTL_D28") (pintype "passive"))
      (node (ref "R64") (pin "1") (pintype "passive"))
    )
    (net (code "80") (name "/QSFP4_LPMODE") (class "Default")
      (node (ref "J4") (pin "D31") (pinfunction "LPMODE_D31") (pintype "passive"))
    )
    (net (code "81") (name "/QSFP4_MODPRSL") (class "Default")
      (node (ref "J4") (pin "D27") (pinfunction "MODPRSL_D27") (pintype "passive"))
      (node (ref "R63") (pin "1") (pintype "passive"))
    )
    (net (code "82") (name "/QSFP4_MODSELL") (class "Default")
      (node (ref "J4") (pin "D8") (pinfunction "MODSELL_D8") (pintype "passive"))
    )
    (net (code "83") (name "/QSFP4_RESETL") (class "Default")
      (node (ref "J4") (pin "D9") (pinfunction "RESETL_D9") (pintype "passive"))
      (node (ref "R62") (pin "1") (pintype "passive"))
    )
    (net (code "84") (name "/QSFP4_RX1_N") (class "Default")
      (node (ref "J4") (pin "D18") (pinfunction "RX1N_D18") (pintype "passive"))
    )
    (net (code "85") (name "/QSFP4_RX1_P") (class "Default")
      (node (ref "J4") (pin "D17") (pinfunction "RX1P_D17") (pintype "passive"))
    )
    (net (code "86") (name "/QSFP4_RX2_N") (class "Default")
      (node (ref "J4") (pin "D21") (pinfunction "RX2N_D21") (pintype "passive"))
    )
    (net (code "87") (name "/QSFP4_RX2_P") (class "Default")
      (node (ref "J4") (pin "D22") (pinfunction "RX2P_D22") (pintype "passive"))
    )
    (net (code "88") (name "/QSFP4_RX3_N") (class "Default")
      (node (ref "J4") (pin "D15") (pinfunction "RX3N_D15") (pintype "passive"))
    )
    (net (code "89") (name "/QSFP4_RX3_P") (class "Default")
      (node (ref "J4") (pin "D14") (pinfunction "RX3P_D14") (pintype "passive"))
    )
    (net (code "90") (name "/QSFP4_RX4_N") (class "Default")
      (node (ref "J4") (pin "D24") (pinfunction "RX4N_D24") (pintype "passive"))
    )
    (net (code "91") (name "/QSFP4_RX4_P") (class "Default")
      (node (ref "J4") (pin "D25") (pinfunction "RX4P_D25") (pintype "passive"))
    )
    (net (code "92") (name "/QSFP4_SCL") (class "Default")
      (node (ref "J4") (pin "D11") (pinfunction "SCL_D11") (pintype "input"))
    )
    (net (code "93") (name "/QSFP4_SDA") (class "Default")
      (node (ref "J4") (pin "D12") (pinfunction "SDA_D12") (pintype "bidirectional"))
    )
    (net (code "94") (name "/QSFP4_TX1_N") (class "Default")
      (node (ref "J4") (pin "D37") (pinfunction "TX1N_D37") (pintype "passive"))
    )
    (net (code "95") (name "/QSFP4_TX1_P") (class "Default")
      (node (ref "J4") (pin "D36") (pinfunction "TX1P_D36") (pintype "passive"))
    )
    (net (code "96") (name "/QSFP4_TX2_N") (class "Default")
      (node (ref "J4") (pin "D2") (pinfunction "TX2N_D2") (pintype "passive"))
    )
    (net (code "97") (name "/QSFP4_TX2_P") (class "Default")
      (node (ref "J4") (pin "D3") (pinfunction "TX2P_D3") (pintype "passive"))
    )
    (net (code "98") (name "/QSFP4_TX3_N") (class "Default")
      (node (ref "J4") (pin "D34") (pinfunction "TX3N_D34") (pintype "passive"))
    )
    (net (code "99") (name "/QSFP4_TX3_P") (class "Default")
      (node (ref "J4") (pin "D33") (pinfunction "TX3P_D33") (pintype "passive"))
    )
    (net (code "100") (name "/QSFP4_TX4_N") (class "Default")
      (node (ref "J4") (pin "D5") (pinfunction "TX4N_D5") (pintype "passive"))
    )
    (net (code "101") (name "/QSFP4_TX4_P") (class "Default")
      (node (ref "J4") (pin "D6") (pinfunction "TX4P_D6") (pintype "passive"))
    )
    (net (code "102") (name "/QSFP4_VCCI") (class "Default")
      (node (ref "C62") (pin "2") (pinfunction "2_2") (pintype "passive"))
      (node (ref "C63") (pin "2") (pinfunction "2_2") (pintype "passive"))
      (node (ref "FB14") (pin "2") (pintype "passive"))
      (node (ref "J4") (pin "D30") (pinfunction "VCCI_D30") (pintype "power_in"))
    )
    (net (code "103") (name "/QSFP4_VCCRX") (class "Default")
      (node (ref "C54") (pin "2") (pinfunction "2_2") (pintype "passive"))
      (node (ref "C55") (pin "2") (pinfunction "2_2") (pintype "passive"))
      (node (ref "FB10") (pin "2") (pintype "passive"))
      (node (ref "J4") (pin "D10") (pinfunction "VCCRX_D10") (pintype "power_in"))
    )
    (net (code "104") (name "/QSFP4_VCCTX") (class "Default")
      (node (ref "C58") (pin "2") (pinfunction "2_2") (pintype "passive"))
      (node (ref "C59") (pin "2") (pinfunction "2_2") (pintype "passive"))
      (node (ref "FB12") (pin "2") (pintype "passive"))
      (node (ref "J4") (pin "D29") (pinfunction "VCCTX_D29") (pintype "power_in"))
    )
    (net (code "105") (name "GND") (class "Default")
      (node (ref "C32") (pin "1") (pinfunction "1_1") (pintype "passive"))
      (node (ref "C33") (pin "1") (pinfunction "1_1") (pintype "passive"))
      (node (ref "C34") (pin "1") (pinfunction "1_1") (pintype "passive"))
      (node (ref "C35") (pin "1") (pinfunction "1_1") (pintype "passive"))
      (node (ref "C36") (pin "1") (pinfunction "1_1") (pintype "passive"))
      (node (ref "C37") (pin "1") (pinfunction "1_1") (pintype "passive"))
      (node (ref "C38") (pin "1") (pinfunction "1_1") (pintype "passive"))
      (node (ref "C39") (pin "1") (pinfunction "1_1") (pintype "passive"))
      (node (ref "C40") (pin "1") (pinfunction "1_1") (pintype "passive"))
      (node (ref "C41") (pin "1") (pinfunction "1_1") (pintype "passive"))
      (node (ref "C42") (pin "1") (pinfunction "1_1") (pintype "passive"))
      (node (ref "C43") (pin "1") (pinfunction "1_1") (pintype "passive"))
      (node (ref "C44") (pin "1") (pinfunction "1_1") (pintype "passive"))
      (node (ref "C45") (pin "1") (pinfunction "1_1") (pintype "passive"))
      (node (ref "C46") (pin "1") (pinfunction "1_1") (pintype "passive"))
      (node (ref "C47") (pin "1") (pinfunction "1_1") (pintype "passive"))
      (node (ref "C48") (pin "1") (pinfunction "1_1") (pintype "passive"))
      (node (ref "C49") (pin "1") (pinfunction "1_1") (pintype "passive"))
      (node (ref "C50") (pin "1") (pinfunction "1_1") (pintype "passive"))
      (node (ref "C51") (pin "1") (pinfunction "1_1") (pintype "passive"))
      (node (ref "C52") (pin "1") (pinfunction "1_1") (pintype "passive"))
      (node (ref "C53") (pin "1") (pinfunction "1_1") (pintype "passive"))
      (node (ref "C54") (pin "1") (pinfunction "1_1") (pintype "passive"))
      (node (ref "C55") (pin "1") (pinfunction "1_1") (pintype "passive"))
      (node (ref "C56") (pin "1") (pinfunction "1_1") (pintype "passive"))
      (node (ref "C57") (pin "1") (pinfunction "1_1") (pintype "passive"))
      (node (ref "C58") (pin "1") (pinfunction "1_1") (pintype "passive"))
      (node (ref "C59") (pin "1") (pinfunction "1_1") (pintype "passive"))
      (node (ref "C60") (pin "1") (pinfunction "1_1") (pintype "passive"))
      (node (ref "C61") (pin "1") (pinfunction "1_1") (pintype "passive"))
      (node (ref "C62") (pin "1") (pinfunction "1_1") (pintype "passive"))
      (node (ref "C63") (pin "1") (pinfunction "1_1") (pintype "passive"))
      (node (ref "J4") (pin "A1") (pinfunction "GND1_A1") (pintype "power_in"))
      (node (ref "J4") (pin "A13") (pinfunction "GND4_A13") (pintype "power_in"))
      (node (ref "J4") (pin "A16") (pinfunction "GND5_A16") (pintype "power_in"))
      (node (ref "J4") (pin "A19") (pinfunction "GND6_A19") (pintype "power_in"))
      (node (ref "J4") (pin "A20") (pinfunction "GND7_A20") (pintype "power_in"))
      (node (ref "J4") (pin "A23") (pinfunction "GND8_A23") (pintype "power_in"))
      (node (ref "J4") (pin "A26") (pinfunction "GND9_A26") (pintype "power_in"))
      (node (ref "J4") (pin "A32") (pinfunction "GND10_A32") (pintype "power_in"))
      (node (ref "J4") (pin "A35") (pinfunction "GND11_A35") (pintype "power_in"))
      (node (ref "J4") (pin "A38") (pinfunction "GND12_A38") (pintype "power_in"))
      (node (ref "J4") (pin "A4") (pinfunction "GND2_A4") (pintype "power_in"))
      (node (ref "J4") (pin "A7") (pinfunction "GND3_A7") (pintype "power_in"))
      (node (ref "J4") (pin "B1") (pinfunction "GND1_B1") (pintype "power_in"))
      (node (ref "J4") (pin "B13") (pinfunction "GND4_B13") (pintype "power_in"))
      (node (ref "J4") (pin "B16") (pinfunction "GND5_B16") (pintype "power_in"))
      (node (ref "J4") (pin "B19") (pinfunction "GND6_B19") (pintype "power_in"))
      (node (ref "J4") (pin "B20") (pinfunction "GND7_B20") (pintype "power_in"))
      (node (ref "J4") (pin "B23") (pinfunction "GND8_B23") (pintype "power_in"))
      (node (ref "J4") (pin "B26") (pinfunction "GND9_B26") (pintype "power_in"))
      (node (ref "J4") (pin "B32") (pinfunction "GND10_B32") (pintype "power_in"))
      (node (ref "J4") (pin "B35") (pinfunction "GND11_B35") (pintype "power_in"))
      (node (ref "J4") (pin "B38") (pinfunction "GND12_B38") (pintype "power_in"))
      (node (ref "J4") (pin "B4") (pinfunction "GND2_B4") (pintype "power_in"))
      (node (ref "J4") (pin "B7") (pinfunction "GND3_B7") (pintype "power_in"))
      (node (ref "J4") (pin "C1") (pinfunction "GND1_C1") (pintype "power_in"))
      (node (ref "J4") (pin "C13") (pinfunction "GND4_C13") (pintype "power_in"))
      (node (ref "J4") (pin "C16") (pinfunction "GND5_C16") (pintype "power_in"))
      (node (ref "J4") (pin "C19") (pinfunction "GND6_C19") (pintype "power_in"))
      (node (ref "J4") (pin "C20") (pinfunction "GND7_C20") (pintype "power_in"))
      (node (ref "J4") (pin "C23") (pinfunction "GND8_C23") (pintype "power_in"))
      (node (ref "J4") (pin "C26") (pinfunction "GND9_C26") (pintype "power_in"))
      (node (ref "J4") (pin "C32") (pinfunction "GND10_C32") (pintype "power_in"))
      (node (ref "J4") (pin "C35") (pinfunction "GND11_C35") (pintype "power_in"))
      (node (ref "J4") (pin "C38") (pinfunction "GND12_C38") (pintype "power_in"))
      (node (ref "J4") (pin "C4") (pinfunction "GND2_C4") (pintype "power_in"))
      (node (ref "J4") (pin "C7") (pinfunction "GND3_C7") (pintype "power_in"))
      (node (ref "J4") (pin "D1") (pinfunction "GND1_D1") (pintype "power_in"))
      (node (ref "J4") (pin "D13") (pinfunction "GND4_D13") (pintype "power_in"))
      (node (ref "J4") (pin "D16") (pinfunction "GND5_D16") (pintype "power_in"))
      (node (ref "J4") (pin "D19") (pinfunction "GND6_D19") (pintype "power_in"))
      (node (ref "J4") (pin "D20") (pinfunction "GND7_D20") (pintype "power_in"))
      (node (ref "J4") (pin "D23") (pinfunction "GND8_D23") (pintype "power_in"))
      (node (ref "J4") (pin "D26") (pinfunction "GND9_D26") (pintype "power_in"))
      (node (ref "J4") (pin "D32") (pinfunction "GND10_D32") (pintype "power_in"))
      (node (ref "J4") (pin "D35") (pinfunction "GND11_D35") (pintype "power_in"))
      (node (ref "J4") (pin "D38") (pinfunction "GND12_D38") (pintype "power_in"))
      (node (ref "J4") (pin "D4") (pinfunction "GND2_D4") (pintype "power_in"))
      (node (ref "J4") (pin "D7") (pinfunction "GND3_D7") (pintype "power_in"))
    )
    (net (code "106") (name "UTIL_3V3") (class "Default")
      (node (ref "C34") (pin "2") (pinfunction "2_2") (pintype "passive"))
      (node (ref "C35") (pin "2") (pinfunction "2_2") (pintype "passive"))
      (node (ref "C36") (pin "2") (pinfunction "2_2") (pintype "passive"))
      (node (ref "C37") (pin "2") (pinfunction "2_2") (pintype "passive"))
      (node (ref "C48") (pin "2") (pinfunction "2_2") (pintype "passive"))
      (node (ref "C49") (pin "2") (pinfunction "2_2") (pintype "passive"))
      (node (ref "C52") (pin "2") (pinfunction "2_2") (pintype "passive"))
      (node (ref "C53") (pin "2") (pinfunction "2_2") (pintype "passive"))
      (node (ref "FB10") (pin "1") (pintype "passive"))
      (node (ref "FB11") (pin "1") (pintype "passive"))
      (node (ref "FB12") (pin "1") (pintype "passive"))
      (node (ref "FB13") (pin "1") (pintype "passive"))
      (node (ref "FB14") (pin "1") (pintype "passive"))
      (node (ref "FB3") (pin "1") (pintype "passive"))
      (node (ref "FB4") (pin "1") (pintype "passive"))
      (node (ref "FB5") (pin "1") (pintype "passive"))
      (node (ref "FB6") (pin "1") (pintype "passive"))
      (node (ref "FB7") (pin "1") (pintype "passive"))
      (node (ref "FB8") (pin "1") (pintype "passive"))
      (node (ref "FB9") (pin "1") (pintype "passive"))
      (node (ref "R53") (pin "2") (pintype "passive"))
      (node (ref "R54") (pin "2") (pintype "passive"))
      (node (ref "R55") (pin "2") (pintype "passive"))
      (node (ref "R56") (pin "2") (pintype "passive"))
      (node (ref "R57") (pin "2") (pintype "passive"))
      (node (ref "R58") (pin "2") (pintype "passive"))
      (node (ref "R59") (pin "2") (pintype "passive"))
      (node (ref "R60") (pin "2") (pintype "passive"))
      (node (ref "R61") (pin "2") (pintype "passive"))
      (node (ref "R62") (pin "2") (pintype "passive"))
      (node (ref "R63") (pin "2") (pintype "passive"))
      (node (ref "R64") (pin "2") (pintype "passive"))
    )
  )
)
